# 3.net
KiCad netlist of a schematic drawn in Altium Designer
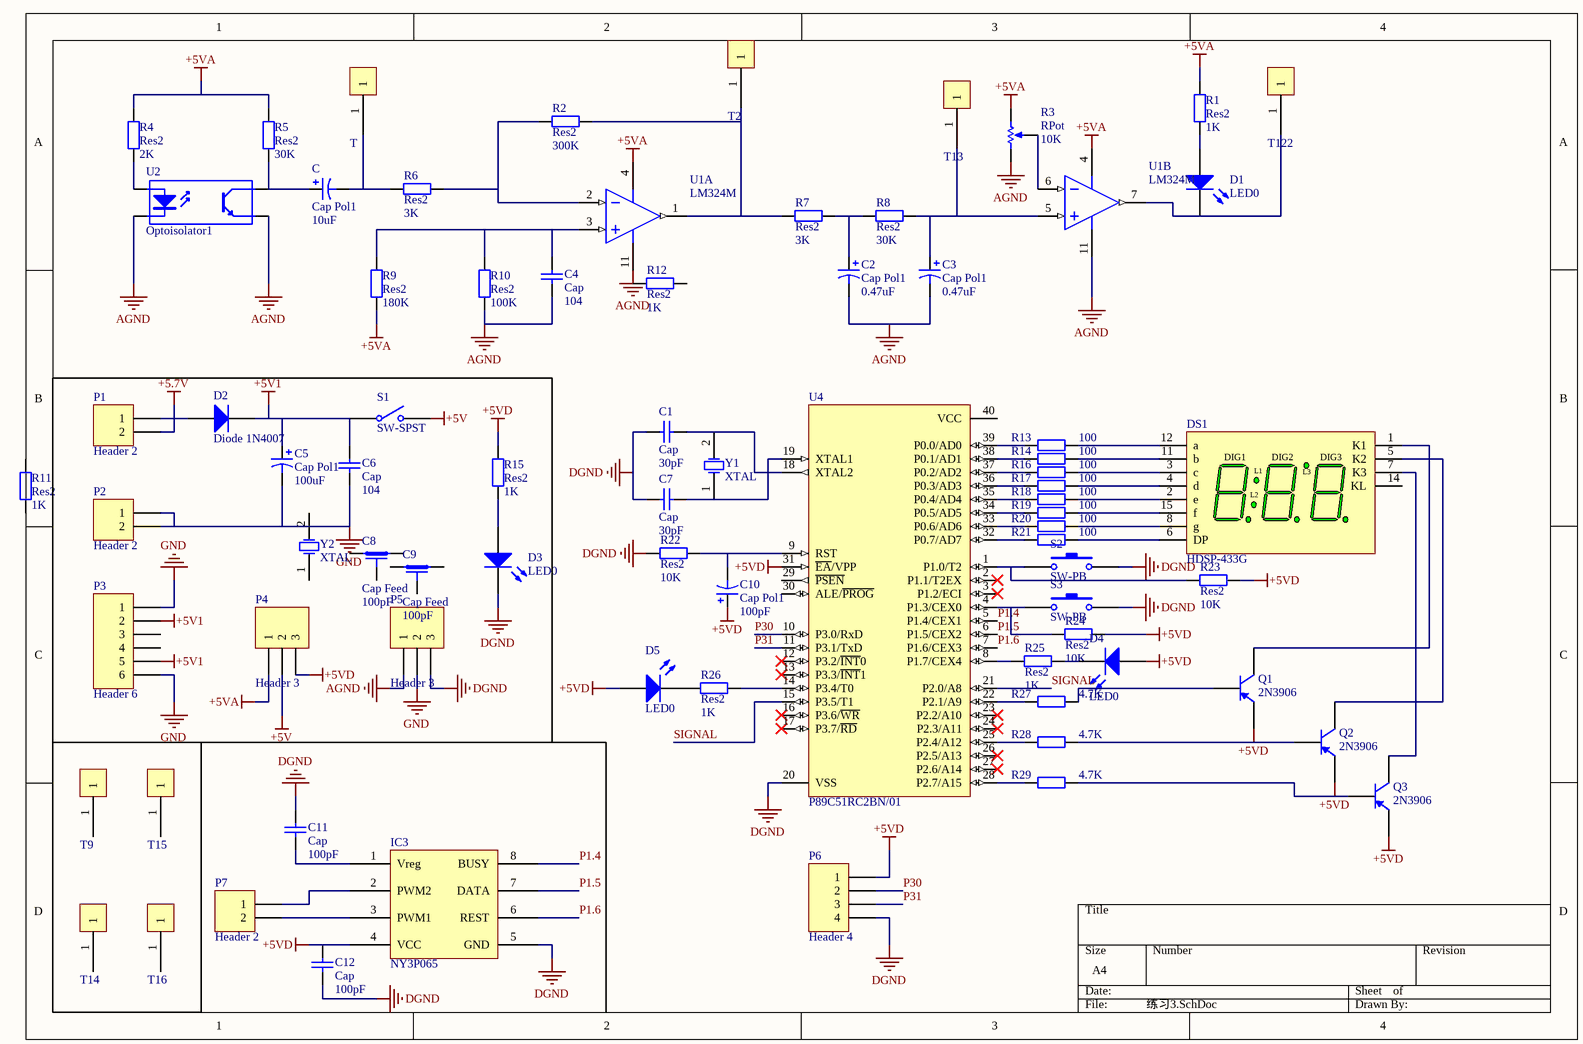
[diagram p0: 练习3.SchDoc]

(export (version "E")
  (design (tool "Eeschema 10.0.6"))
  (components
    (comp (ref "C")
      (value "Cap Pol1")
      (footprint "RB7.6-15")
      (description "Polarized Capacitor (Radial)")
      (fields (field (name "ALTIUM_VALUE") "10uF") (field (name "PUBLISHER") "Altium Limited"))
      (libsource (lib "Miscellaneous Devices") (part "Cap Pol1"))
    )
    (comp (ref "C1")
      (value "Cap")
      (footprint "RAD-0.3")
      (description "Capacitor")
      (fields (field (name "ALTIUM_VALUE") "30pF") (field (name "PUBLISHER") "Altium Limited"))
      (libsource (lib "Miscellaneous Devices") (part "Cap"))
    )
    (comp (ref "C2")
      (value "Cap Pol1")
      (footprint "RB7.6-15")
      (description "Polarized Capacitor (Radial)")
      (fields (field (name "ALTIUM_VALUE") "0.47uF") (field (name "PUBLISHER") "Altium Limited"))
      (libsource (lib "Miscellaneous Devices") (part "Cap Pol1"))
    )
    (comp (ref "C3")
      (value "Cap Pol1")
      (footprint "RB7.6-15")
      (description "Polarized Capacitor (Radial)")
      (fields (field (name "ALTIUM_VALUE") "0.47uF") (field (name "PUBLISHER") "Altium Limited"))
      (libsource (lib "Miscellaneous Devices") (part "Cap Pol1"))
    )
    (comp (ref "C4")
      (value "Cap")
      (footprint "RAD-0.3")
      (description "Capacitor")
      (fields (field (name "ALTIUM_VALUE") "104") (field (name "PUBLISHER") "Altium Limited"))
      (libsource (lib "Miscellaneous Devices") (part "Cap"))
    )
    (comp (ref "C5")
      (value "Cap Pol1")
      (footprint "RB7.6-15")
      (description "Polarized Capacitor (Radial)")
      (fields (field (name "ALTIUM_VALUE") "100uF") (field (name "PUBLISHER") "Altium Limited"))
      (libsource (lib "Miscellaneous Devices") (part "Cap Pol1"))
    )
    (comp (ref "C6")
      (value "Cap")
      (footprint "RAD-0.3")
      (description "Capacitor")
      (fields (field (name "ALTIUM_VALUE") "104") (field (name "PUBLISHER") "Altium Limited"))
      (libsource (lib "Miscellaneous Devices") (part "Cap"))
    )
    (comp (ref "C7")
      (value "Cap")
      (footprint "RAD-0.3")
      (description "Capacitor")
      (fields (field (name "ALTIUM_VALUE") "30pF") (field (name "PUBLISHER") "Altium Limited"))
      (libsource (lib "Miscellaneous Devices") (part "Cap"))
    )
    (comp (ref "C8")
      (value "Cap Feed")
      (footprint "VR4")
      (description "Feed-Through Capacitor")
      (fields (field (name "ALTIUM_VALUE") "100pF") (field (name "PUBLISHER") "Altium Limited"))
      (libsource (lib "Miscellaneous Devices") (part "Cap Feed"))
    )
    (comp (ref "C9")
      (value "Cap Feed")
      (footprint "VR4")
      (description "Feed-Through Capacitor")
      (fields (field (name "ALTIUM_VALUE") "100pF") (field (name "PUBLISHER") "Altium Limited"))
      (libsource (lib "Miscellaneous Devices") (part "Cap Feed"))
    )
    (comp (ref "C10")
      (value "Cap Pol1")
      (footprint "RB7.6-15")
      (description "Polarized Capacitor (Radial)")
      (fields (field (name "ALTIUM_VALUE") "100pF") (field (name "PUBLISHER") "Altium Limited"))
      (libsource (lib "Miscellaneous Devices") (part "Cap Pol1"))
    )
    (comp (ref "C11")
      (value "Cap")
      (footprint "RAD-0.3")
      (description "Capacitor")
      (fields (field (name "ALTIUM_VALUE") "100pF") (field (name "PUBLISHER") "Altium Limited"))
      (libsource (lib "Miscellaneous Devices") (part "Cap"))
    )
    (comp (ref "C12")
      (value "Cap")
      (footprint "RAD-0.3")
      (description "Capacitor")
      (fields (field (name "ALTIUM_VALUE") "100pF") (field (name "PUBLISHER") "Altium Limited"))
      (libsource (lib "Miscellaneous Devices") (part "Cap"))
    )
    (comp (ref "D1")
      (value "LED0")
      (footprint "LED-0")
      (description "Typical INFRARED GaAs LED")
      (fields (field (name "PUBLISHER") "Altium Limited"))
      (libsource (lib "Miscellaneous Devices") (part "LED0"))
    )
    (comp (ref "D2")
      (value "Diode 1N4007")
      (footprint "DO-41")
      (description "1 Amp General Purpose Rectifier")
      (fields (field (name "PUBLISHER") "Altium Limited"))
      (libsource (lib "Miscellaneous Devices") (part "Diode 1N4007"))
    )
    (comp (ref "D3")
      (value "LED0")
      (footprint "LED-0")
      (description "Typical INFRARED GaAs LED")
      (fields (field (name "PUBLISHER") "Altium Limited"))
      (libsource (lib "Miscellaneous Devices") (part "LED0"))
    )
    (comp (ref "D4")
      (value "LED0")
      (footprint "LED-0")
      (description "Typical INFRARED GaAs LED")
      (fields (field (name "PUBLISHER") "Altium Limited"))
      (libsource (lib "Miscellaneous Devices") (part "LED0"))
    )
    (comp (ref "D5")
      (value "LED0")
      (footprint "LED-0")
      (description "Typical INFRARED GaAs LED")
      (fields (field (name "PUBLISHER") "Altium Limited"))
      (libsource (lib "Miscellaneous Devices") (part "LED0"))
    )
    (comp (ref "DS1")
      (value "HDSP-433G")
      (footprint "HDSP-4")
      (description "10 mm Gray Surface 7-Segment Display: 3-Digit with 2-Colons, CC, Slim Font, Untinted-Diffused")
      (fields (field (name "PUBLISHER") "Altium Limited"))
      (libsource (lib "Agilent LED Display 7-Segment, 3-Digit") (part "HDSP-433G"))
    )
    (comp (ref "IC3") (value "NY3P065") (footprint "SO8MY") (libsource (lib "EPL Scblib") (part "SOUND")))
    (comp (ref "P1")
      (value "Header 2")
      (footprint "HDR1X2")
      (description "Header, 2-Pin")
      (fields (field (name "PUBLISHER") "Altium Limited"))
      (libsource (lib "Miscellaneous Connectors") (part "Header 2"))
    )
    (comp (ref "P2")
      (value "Header 2")
      (footprint "HDR1X2")
      (description "Header, 2-Pin")
      (fields (field (name "PUBLISHER") "Altium Limited"))
      (libsource (lib "Miscellaneous Connectors") (part "Header 2"))
    )
    (comp (ref "P3")
      (value "Header 6")
      (footprint "HDR1X6")
      (description "Header, 6-Pin")
      (fields (field (name "PUBLISHER") "Altium Limited"))
      (libsource (lib "Miscellaneous Connectors") (part "Header 6"))
    )
    (comp (ref "P4")
      (value "Header 3")
      (footprint "HDR1X3")
      (description "Header, 3-Pin")
      (fields (field (name "PUBLISHER") "Altium Limited"))
      (libsource (lib "Miscellaneous Connectors") (part "Header 3"))
    )
    (comp (ref "P5")
      (value "Header 3")
      (footprint "HDR1X3")
      (description "Header, 3-Pin")
      (fields (field (name "PUBLISHER") "Altium Limited"))
      (libsource (lib "Miscellaneous Connectors") (part "Header 3"))
    )
    (comp (ref "P6")
      (value "Header 4")
      (footprint "HDR1X4")
      (description "Header, 4-Pin")
      (fields (field (name "PUBLISHER") "Altium Limited"))
      (libsource (lib "Miscellaneous Connectors") (part "Header 4"))
    )
    (comp (ref "P7")
      (value "Header 2")
      (footprint "HDR1X2")
      (description "Header, 2-Pin")
      (fields (field (name "PUBLISHER") "Altium Limited"))
      (libsource (lib "Miscellaneous Connectors") (part "Header 2"))
    )
    (comp (ref "Q1")
      (value "2N3906")
      (footprint "TO-92A")
      (description "PNP General Purpose Amplifier")
      (fields (field (name "PUBLISHER") "Altium Limited"))
      (libsource (lib "Miscellaneous Devices") (part "2N3906"))
    )
    (comp (ref "Q2")
      (value "2N3906")
      (footprint "TO-92A")
      (description "PNP General Purpose Amplifier")
      (fields (field (name "PUBLISHER") "Altium Limited"))
      (libsource (lib "Miscellaneous Devices") (part "2N3906"))
    )
    (comp (ref "Q3")
      (value "2N3906")
      (footprint "TO-92A")
      (description "PNP General Purpose Amplifier")
      (fields (field (name "PUBLISHER") "Altium Limited"))
      (libsource (lib "Miscellaneous Devices") (part "2N3906"))
    )
    (comp (ref "R1")
      (value "Res2")
      (footprint "AXIAL-0.4")
      (description "Resistor")
      (fields (field (name "ALTIUM_VALUE") "1K") (field (name "PUBLISHER") "Altium Limited"))
      (libsource (lib "") (part "Res2_2"))
    )
    (comp (ref "R2")
      (value "Res2")
      (footprint "AXIAL-0.4")
      (description "Resistor")
      (fields (field (name "ALTIUM_VALUE") "300K") (field (name "PUBLISHER") "Altium Limited"))
      (libsource (lib "Miscellaneous Devices") (part "Res2"))
    )
    (comp (ref "R3")
      (value "RPot")
      (footprint "VR5")
      (description "Potentiometer")
      (fields (field (name "ALTIUM_VALUE") "10K") (field (name "PUBLISHER") "Altium Limited"))
      (libsource (lib "Miscellaneous Devices") (part "RPot"))
    )
    (comp (ref "R4")
      (value "Res2")
      (footprint "AXIAL-0.4")
      (description "Resistor")
      (fields (field (name "ALTIUM_VALUE") "2K") (field (name "PUBLISHER") "Altium Limited"))
      (libsource (lib "") (part "Res2_2"))
    )
    (comp (ref "R5")
      (value "Res2")
      (footprint "AXIAL-0.4")
      (description "Resistor")
      (fields (field (name "ALTIUM_VALUE") "30K") (field (name "PUBLISHER") "Altium Limited"))
      (libsource (lib "") (part "Res2_2"))
    )
    (comp (ref "R6")
      (value "Res2")
      (footprint "AXIAL-0.4")
      (description "Resistor")
      (fields (field (name "ALTIUM_VALUE") "3K") (field (name "PUBLISHER") "Altium Limited"))
      (libsource (lib "Miscellaneous Devices") (part "Res2"))
    )
    (comp (ref "R7")
      (value "Res2")
      (footprint "AXIAL-0.4")
      (description "Resistor")
      (fields (field (name "ALTIUM_VALUE") "3K") (field (name "PUBLISHER") "Altium Limited"))
      (libsource (lib "Miscellaneous Devices") (part "Res2"))
    )
    (comp (ref "R8")
      (value "Res2")
      (footprint "AXIAL-0.4")
      (description "Resistor")
      (fields (field (name "ALTIUM_VALUE") "30K") (field (name "PUBLISHER") "Altium Limited"))
      (libsource (lib "Miscellaneous Devices") (part "Res2"))
    )
    (comp (ref "R9")
      (value "Res2")
      (footprint "AXIAL-0.4")
      (description "Resistor")
      (fields (field (name "ALTIUM_VALUE") "180K") (field (name "PUBLISHER") "Altium Limited"))
      (libsource (lib "") (part "Res2_1"))
    )
    (comp (ref "R10")
      (value "Res2")
      (footprint "AXIAL-0.4")
      (description "Resistor")
      (fields (field (name "ALTIUM_VALUE") "100K") (field (name "PUBLISHER") "Altium Limited"))
      (libsource (lib "") (part "Res2_1"))
    )
    (comp (ref "R11")
      (value "Res2")
      (footprint "AXIAL-0.4")
      (description "Resistor")
      (fields (field (name "ALTIUM_VALUE") "1K") (field (name "PUBLISHER") "Altium Limited"))
      (libsource (lib "") (part "Res2_1"))
    )
    (comp (ref "R12")
      (value "Res2")
      (footprint "AXIAL-0.4")
      (description "Resistor")
      (fields (field (name "ALTIUM_VALUE") "1K") (field (name "PUBLISHER") "Altium Limited"))
      (libsource (lib "Miscellaneous Devices") (part "Res2"))
    )
    (comp (ref "R13")
      (value "100")
      (footprint "AXIAL-0.4")
      (description "Resistor")
      (fields (field (name "PUBLISHER") "Altium Limited"))
      (libsource (lib "Miscellaneous Devices") (part "Res2"))
    )
    (comp (ref "R14")
      (value "100")
      (footprint "AXIAL-0.4")
      (description "Resistor")
      (fields (field (name "PUBLISHER") "Altium Limited"))
      (libsource (lib "Miscellaneous Devices") (part "Res2"))
    )
    (comp (ref "R15")
      (value "Res2")
      (footprint "AXIAL-0.4")
      (description "Resistor")
      (fields (field (name "ALTIUM_VALUE") "1K") (field (name "PUBLISHER") "Altium Limited"))
      (libsource (lib "") (part "Res2_1"))
    )
    (comp (ref "R16")
      (value "100")
      (footprint "AXIAL-0.4")
      (description "Resistor")
      (fields (field (name "PUBLISHER") "Altium Limited"))
      (libsource (lib "Miscellaneous Devices") (part "Res2"))
    )
    (comp (ref "R17")
      (value "100")
      (footprint "AXIAL-0.4")
      (description "Resistor")
      (fields (field (name "PUBLISHER") "Altium Limited"))
      (libsource (lib "Miscellaneous Devices") (part "Res2"))
    )
    (comp (ref "R18")
      (value "100")
      (footprint "AXIAL-0.4")
      (description "Resistor")
      (fields (field (name "PUBLISHER") "Altium Limited"))
      (libsource (lib "Miscellaneous Devices") (part "Res2"))
    )
    (comp (ref "R19")
      (value "100")
      (footprint "AXIAL-0.4")
      (description "Resistor")
      (fields (field (name "PUBLISHER") "Altium Limited"))
      (libsource (lib "Miscellaneous Devices") (part "Res2"))
    )
    (comp (ref "R20")
      (value "100")
      (footprint "AXIAL-0.4")
      (description "Resistor")
      (fields (field (name "PUBLISHER") "Altium Limited"))
      (libsource (lib "Miscellaneous Devices") (part "Res2"))
    )
    (comp (ref "R21")
      (value "100")
      (footprint "AXIAL-0.4")
      (description "Resistor")
      (fields (field (name "PUBLISHER") "Altium Limited"))
      (libsource (lib "Miscellaneous Devices") (part "Res2"))
    )
    (comp (ref "R22")
      (value "Res2")
      (footprint "AXIAL-0.4")
      (description "Resistor")
      (fields (field (name "ALTIUM_VALUE") "10K") (field (name "PUBLISHER") "Altium Limited"))
      (libsource (lib "Miscellaneous Devices") (part "Res2"))
    )
    (comp (ref "R23")
      (value "Res2")
      (footprint "AXIAL-0.4")
      (description "Resistor")
      (fields (field (name "ALTIUM_VALUE") "10K") (field (name "PUBLISHER") "Altium Limited"))
      (libsource (lib "Miscellaneous Devices") (part "Res2"))
    )
    (comp (ref "R24")
      (value "Res2")
      (footprint "AXIAL-0.4")
      (description "Resistor")
      (fields (field (name "ALTIUM_VALUE") "10K") (field (name "PUBLISHER") "Altium Limited"))
      (libsource (lib "Miscellaneous Devices") (part "Res2"))
    )
    (comp (ref "R25")
      (value "Res2")
      (footprint "AXIAL-0.4")
      (description "Resistor")
      (fields (field (name "ALTIUM_VALUE") "1K") (field (name "PUBLISHER") "Altium Limited"))
      (libsource (lib "Miscellaneous Devices") (part "Res2"))
    )
    (comp (ref "R26")
      (value "Res2")
      (footprint "AXIAL-0.4")
      (description "Resistor")
      (fields (field (name "ALTIUM_VALUE") "1K") (field (name "PUBLISHER") "Altium Limited"))
      (libsource (lib "Miscellaneous Devices") (part "Res2"))
    )
    (comp (ref "R27")
      (value "4.7K")
      (footprint "AXIAL-0.4")
      (description "Resistor")
      (fields (field (name "PUBLISHER") "Altium Limited"))
      (libsource (lib "Miscellaneous Devices") (part "Res2"))
    )
    (comp (ref "R28")
      (value "4.7K")
      (footprint "AXIAL-0.4")
      (description "Resistor")
      (fields (field (name "PUBLISHER") "Altium Limited"))
      (libsource (lib "Miscellaneous Devices") (part "Res2"))
    )
    (comp (ref "R29")
      (value "4.7K")
      (footprint "AXIAL-0.4")
      (description "Resistor")
      (fields (field (name "PUBLISHER") "Altium Limited"))
      (libsource (lib "Miscellaneous Devices") (part "Res2"))
    )
    (comp (ref "S1")
      (value "SW-SPST")
      (footprint "SPST-2")
      (description "Single-Pole, Single-Throw Switch")
      (fields (field (name "PUBLISHER") "Altium Limited"))
      (libsource (lib "Miscellaneous Devices") (part "SW-SPST"))
    )
    (comp (ref "S2")
      (value "SW-PB")
      (footprint "SPST-2")
      (description "Switch")
      (fields (field (name "PUBLISHER") "Altium Limited"))
      (libsource (lib "Miscellaneous Devices") (part "SW-PB"))
    )
    (comp (ref "S3")
      (value "SW-PB")
      (footprint "SPST-2")
      (description "Switch")
      (fields (field (name "PUBLISHER") "Altium Limited"))
      (libsource (lib "Miscellaneous Devices") (part "SW-PB"))
    )
    (comp (ref "T") (value "TEST") (footprint "SIP1") (libsource (lib "EPL Scblib") (part "TEST")))
    (comp (ref "T2") (value "TEST") (footprint "SIP1") (libsource (lib "EPL Scblib") (part "TEST")))
    (comp (ref "T9") (value "TEST") (footprint "SIP1") (libsource (lib "EPL Scblib") (part "TEST")))
    (comp (ref "T13") (value "TEST") (footprint "SIP1") (libsource (lib "EPL Scblib") (part "TEST")))
    (comp (ref "T14") (value "TEST") (footprint "SIP1") (libsource (lib "EPL Scblib") (part "TEST")))
    (comp (ref "T15") (value "TEST") (footprint "SIP1") (libsource (lib "EPL Scblib") (part "TEST")))
    (comp (ref "T16") (value "TEST") (footprint "SIP1") (libsource (lib "EPL Scblib") (part "TEST")))
    (comp (ref "T122") (value "TEST") (footprint "SIP1") (libsource (lib "EPL Scblib") (part "TEST")))
    (comp (ref "U1")
      (value "LM324M")
      (footprint "M14A_N")
      (description "Low Power Quad Operational Amplifier")
      (fields
        (field (name "MANUFACTURER") "National Semiconductor")
        (field (name "DIGIKEYPARTNUMBER") "LM324MXCT-ND")
        (field (name "PUBLISHER") "Altium Limited")
      )
      (libsource (lib "NSC Amplifier") (part "LM324M"))
    )
    (comp (ref "U2")
      (value "Optoisolator1")
      (footprint "DIP-4")
      (description "4-Pin Phototransistor Optocoupler")
      (fields (field (name "PUBLISHER") "Altium Limited"))
      (libsource (lib "Miscellaneous Devices") (part "Optoisolator1"))
    )
    (comp (ref "U4")
      (value "P89C51RC2BN/01")
      (footprint "SOT129-1")
      (description "80C51 8-Bit Flash Microcontroller Family, 32 kB ISP/IAP Flash with 512 B RAM.")
      (fields (field (name "PUBLISHER") "Altium Limited"))
      (libsource (lib "Philips Microcontroller 8-Bit") (part "P89C51RC2BN/01"))
    )
    (comp (ref "Y1")
      (value "XTAL")
      (footprint "R38")
      (description "Crystal Oscillator")
      (fields (field (name "PUBLISHER") "Altium Limited"))
      (libsource (lib "Miscellaneous Devices") (part "XTAL"))
    )
    (comp (ref "Y2")
      (value "XTAL")
      (footprint "R38")
      (description "Crystal Oscillator")
      (fields (field (name "PUBLISHER") "Altium Limited"))
      (libsource (lib "Miscellaneous Devices") (part "XTAL"))
    )
  )
  (nets
    (net (code "1") (name "+5.7V") (class "Default")
      (node (ref "D2") (pin "1") (pinfunction "A_1") (pintype "passive"))
      (node (ref "P1") (pin "1") (pinfunction "1_1") (pintype "passive"))
      (node (ref "P1") (pin "2") (pinfunction "2_2") (pintype "passive"))
    )
    (net (code "2") (name "+5V") (class "Default")
      (node (ref "P4") (pin "2") (pinfunction "2_2") (pintype "passive"))
      (node (ref "S1") (pin "2") (pinfunction "NO_2") (pintype "passive"))
    )
    (net (code "3") (name "+5V1") (class "Default")
      (node (ref "C5") (pin "1") (pinfunction "1_1") (pintype "passive"))
      (node (ref "C6") (pin "1") (pinfunction "1_1") (pintype "passive"))
      (node (ref "D2") (pin "2") (pinfunction "K_2") (pintype "passive"))
      (node (ref "P3") (pin "2") (pinfunction "2_2") (pintype "passive"))
      (node (ref "P3") (pin "5") (pinfunction "5_5") (pintype "passive"))
      (node (ref "S1") (pin "1") (pinfunction "COMMON_1") (pintype "passive"))
    )
    (net (code "4") (name "+5VA") (class "Default")
      (node (ref "P4") (pin "1") (pinfunction "1_1") (pintype "passive"))
      (node (ref "R1") (pin "2") (pinfunction "2_2") (pintype "passive"))
      (node (ref "R3") (pin "2") (pinfunction "BOT_2") (pintype "passive"))
      (node (ref "R4") (pin "2") (pinfunction "2_2") (pintype "passive"))
      (node (ref "R5") (pin "2") (pinfunction "2_2") (pintype "passive"))
      (node (ref "R9") (pin "2") (pinfunction "2_2") (pintype "passive"))
      (node (ref "U1") (pin "4") (pinfunction "V+_4") (pintype "power_in"))
    )
    (net (code "5") (name "+5VD") (class "Default")
      (node (ref "C10") (pin "1") (pinfunction "1_1") (pintype "passive"))
      (node (ref "C12") (pin "2") (pinfunction "2_2") (pintype "passive"))
      (node (ref "D4") (pin "1") (pinfunction "A_1") (pintype "passive"))
      (node (ref "D5") (pin "1") (pinfunction "A_1") (pintype "passive"))
      (node (ref "IC3") (pin "4") (pinfunction "VCC_4") (pintype "passive"))
      (node (ref "P4") (pin "3") (pinfunction "3_3") (pintype "passive"))
      (node (ref "P6") (pin "1") (pinfunction "1_1") (pintype "passive"))
      (node (ref "Q1") (pin "1") (pinfunction "E_1") (pintype "passive"))
      (node (ref "Q2") (pin "1") (pinfunction "E_1") (pintype "passive"))
      (node (ref "Q3") (pin "1") (pinfunction "E_1") (pintype "passive"))
      (node (ref "R15") (pin "1") (pinfunction "1_1") (pintype "passive"))
      (node (ref "R23") (pin "2") (pinfunction "2_2") (pintype "passive"))
      (node (ref "R24") (pin "2") (pinfunction "2_2") (pintype "passive"))
      (node (ref "U4") (pin "31") (pinfunction "~{EA}/VPP_31") (pintype "input"))
    )
    (net (code "6") (name "/P1.4") (class "Default")
      (node (ref "IC3") (pin "8") (pinfunction "BUSY_8") (pintype "passive"))
      (node (ref "U4") (pin "5") (pinfunction "P1.4/CEX1_5") (pintype "bidirectional"))
    )
    (net (code "7") (name "/P1.5") (class "Default")
      (node (ref "IC3") (pin "7") (pinfunction "DATA_7") (pintype "passive"))
      (node (ref "U4") (pin "6") (pinfunction "P1.5/CEX2_6") (pintype "bidirectional"))
    )
    (net (code "8") (name "/P1.6") (class "Default")
      (node (ref "IC3") (pin "6") (pinfunction "REST_6") (pintype "passive"))
      (node (ref "U4") (pin "7") (pinfunction "P1.6/CEX3_7") (pintype "bidirectional"))
    )
    (net (code "9") (name "/P30") (class "Default")
      (node (ref "P6") (pin "2") (pinfunction "2_2") (pintype "passive"))
      (node (ref "U4") (pin "10") (pinfunction "P3.0/RxD_10") (pintype "bidirectional"))
    )
    (net (code "10") (name "/P31") (class "Default")
      (node (ref "P6") (pin "3") (pinfunction "3_3") (pintype "passive"))
      (node (ref "U4") (pin "11") (pinfunction "P3.1/TxD_11") (pintype "bidirectional"))
    )
    (net (code "11") (name "/SIGNAL") (class "Default")
      (node (ref "U4") (pin "15") (pinfunction "P3.5/T1_15") (pintype "bidirectional"))
      (node (ref "U4") (pin "21") (pinfunction "P2.0/A8_21") (pintype "bidirectional"))
    )
    (net (code "12") (name "AGND") (class "Default")
      (node (ref "C2") (pin "2") (pinfunction "2_2") (pintype "passive"))
      (node (ref "C3") (pin "2") (pinfunction "2_2") (pintype "passive"))
      (node (ref "C4") (pin "1") (pinfunction "1_1") (pintype "passive"))
      (node (ref "P5") (pin "1") (pinfunction "1_1") (pintype "passive"))
      (node (ref "R10") (pin "2") (pinfunction "2_2") (pintype "passive"))
      (node (ref "R3") (pin "1") (pinfunction "TOP_1") (pintype "passive"))
      (node (ref "U1") (pin "11") (pinfunction "GND_11") (pintype "power_in"))
      (node (ref "U2") (pin "2") (pinfunction "K_2") (pintype "passive"))
      (node (ref "U2") (pin "3") (pinfunction "E_3") (pintype "passive"))
    )
    (net (code "13") (name "DGND") (class "Default")
      (node (ref "C1") (pin "1") (pinfunction "1_1") (pintype "passive"))
      (node (ref "C11") (pin "2") (pinfunction "2_2") (pintype "passive"))
      (node (ref "C12") (pin "1") (pinfunction "1_1") (pintype "passive"))
      (node (ref "C7") (pin "2") (pinfunction "2_2") (pintype "passive"))
      (node (ref "D3") (pin "2") (pinfunction "K_2") (pintype "passive"))
      (node (ref "IC3") (pin "5") (pinfunction "GND_5") (pintype "passive"))
      (node (ref "P5") (pin "3") (pinfunction "3_3") (pintype "passive"))
      (node (ref "P6") (pin "4") (pinfunction "4_4") (pintype "passive"))
      (node (ref "R22") (pin "1") (pinfunction "1_1") (pintype "passive"))
      (node (ref "S2") (pin "2") (pinfunction "2_2") (pintype "passive"))
      (node (ref "S3") (pin "2") (pinfunction "2_2") (pintype "passive"))
      (node (ref "U4") (pin "20") (pinfunction "VSS_20") (pintype "power_in"))
    )
    (net (code "14") (name "GND") (class "Default")
      (node (ref "C5") (pin "2") (pinfunction "2_2") (pintype "passive"))
      (node (ref "C6") (pin "2") (pinfunction "2_2") (pintype "passive"))
      (node (ref "P2") (pin "1") (pinfunction "1_1") (pintype "passive"))
      (node (ref "P2") (pin "2") (pinfunction "2_2") (pintype "passive"))
      (node (ref "P3") (pin "1") (pinfunction "1_1") (pintype "passive"))
      (node (ref "P3") (pin "6") (pinfunction "6_6") (pintype "passive"))
      (node (ref "P5") (pin "2") (pinfunction "2_2") (pintype "passive"))
    )
    (net (code "15") (name "Net-(C-Pad2)") (class "Default")
      (node (ref "C") (pin "2") (pinfunction "2_2") (pintype "passive"))
      (node (ref "R6") (pin "1") (pinfunction "1_1") (pintype "passive"))
      (node (ref "T") (pin "1") (pinfunction "1_1") (pintype "passive"))
    )
    (net (code "16") (name "Net-(C2-Pad1)") (class "Default")
      (node (ref "C2") (pin "1") (pinfunction "1_1") (pintype "passive"))
      (node (ref "R7") (pin "2") (pinfunction "2_2") (pintype "passive"))
      (node (ref "R8") (pin "1") (pinfunction "1_1") (pintype "passive"))
    )
    (net (code "17") (name "Net-(D1-A)") (class "Default")
      (node (ref "D1") (pin "1") (pinfunction "A_1") (pintype "passive"))
      (node (ref "R1") (pin "1") (pinfunction "1_1") (pintype "passive"))
    )
    (net (code "18") (name "Net-(D1-K)") (class "Default")
      (node (ref "D1") (pin "2") (pinfunction "K_2") (pintype "passive"))
      (node (ref "T122") (pin "1") (pinfunction "1_1") (pintype "passive"))
      (node (ref "U1") (pin "7") (pinfunction "OUT2_7") (pintype "output"))
    )
    (net (code "19") (name "Net-(D3-A)") (class "Default")
      (node (ref "D3") (pin "1") (pinfunction "A_1") (pintype "passive"))
      (node (ref "R15") (pin "2") (pinfunction "2_2") (pintype "passive"))
    )
    (net (code "20") (name "Net-(D4-K)") (class "Default")
      (node (ref "D4") (pin "2") (pinfunction "K_2") (pintype "passive"))
      (node (ref "R25") (pin "2") (pinfunction "2_2") (pintype "passive"))
    )
    (net (code "21") (name "Net-(D5-K)") (class "Default")
      (node (ref "D5") (pin "2") (pinfunction "K_2") (pintype "passive"))
      (node (ref "R26") (pin "1") (pinfunction "1_1") (pintype "passive"))
    )
    (net (code "22") (name "Net-(DS1-DP)") (class "Default")
      (node (ref "DS1") (pin "6") (pinfunction "DP_6") (pintype "passive"))
      (node (ref "R21") (pin "2") (pinfunction "2_2") (pintype "passive"))
    )
    (net (code "23") (name "Net-(DS1-K1)") (class "Default")
      (node (ref "DS1") (pin "1") (pinfunction "K1_1") (pintype "passive"))
      (node (ref "Q1") (pin "3") (pinfunction "C_3") (pintype "passive"))
    )
    (net (code "24") (name "Net-(DS1-K2)") (class "Default")
      (node (ref "DS1") (pin "5") (pinfunction "K2_5") (pintype "passive"))
      (node (ref "Q2") (pin "3") (pinfunction "C_3") (pintype "passive"))
    )
    (net (code "25") (name "Net-(DS1-K3)") (class "Default")
      (node (ref "DS1") (pin "7") (pinfunction "K3_7") (pintype "passive"))
      (node (ref "Q3") (pin "3") (pinfunction "C_3") (pintype "passive"))
    )
    (net (code "26") (name "Net-(DS1-a)") (class "Default")
      (node (ref "DS1") (pin "12") (pinfunction "a_12") (pintype "passive"))
      (node (ref "R13") (pin "2") (pinfunction "2_2") (pintype "passive"))
    )
    (net (code "27") (name "Net-(DS1-b)") (class "Default")
      (node (ref "DS1") (pin "11") (pinfunction "b_11") (pintype "passive"))
      (node (ref "R14") (pin "2") (pinfunction "2_2") (pintype "passive"))
    )
    (net (code "28") (name "Net-(DS1-c)") (class "Default")
      (node (ref "DS1") (pin "3") (pinfunction "c_3") (pintype "passive"))
      (node (ref "R16") (pin "2") (pinfunction "2_2") (pintype "passive"))
    )
    (net (code "29") (name "Net-(DS1-d)") (class "Default")
      (node (ref "DS1") (pin "4") (pinfunction "d_4") (pintype "passive"))
      (node (ref "R17") (pin "2") (pinfunction "2_2") (pintype "passive"))
    )
    (net (code "30") (name "Net-(DS1-e)") (class "Default")
      (node (ref "DS1") (pin "2") (pinfunction "e_2") (pintype "passive"))
      (node (ref "R18") (pin "2") (pinfunction "2_2") (pintype "passive"))
    )
    (net (code "31") (name "Net-(DS1-f)") (class "Default")
      (node (ref "DS1") (pin "15") (pinfunction "f_15") (pintype "passive"))
      (node (ref "R19") (pin "2") (pinfunction "2_2") (pintype "passive"))
    )
    (net (code "32") (name "Net-(DS1-g)") (class "Default")
      (node (ref "DS1") (pin "8") (pinfunction "g_8") (pintype "passive"))
      (node (ref "R20") (pin "2") (pinfunction "2_2") (pintype "passive"))
    )
    (net (code "33") (name "Net-(IC3-PWM1)") (class "Default")
      (node (ref "IC3") (pin "3") (pinfunction "PWM1_3") (pintype "passive"))
      (node (ref "P7") (pin "2") (pinfunction "2_2") (pintype "passive"))
    )
    (net (code "34") (name "Net-(IC3-PWM2)") (class "Default")
      (node (ref "IC3") (pin "2") (pinfunction "PWM2_2") (pintype "passive"))
      (node (ref "P7") (pin "1") (pinfunction "1_1") (pintype "passive"))
    )
    (net (code "35") (name "Net-(IC3-Vreg)") (class "Default")
      (node (ref "C11") (pin "1") (pinfunction "1_1") (pintype "passive"))
      (node (ref "IC3") (pin "1") (pinfunction "Vreg_1") (pintype "passive"))
    )
    (net (code "36") (name "Net-(Q1-B)") (class "Default")
      (node (ref "Q1") (pin "2") (pinfunction "B_2") (pintype "passive"))
      (node (ref "R27") (pin "2") (pinfunction "2_2") (pintype "passive"))
    )
    (net (code "37") (name "Net-(Q2-B)") (class "Default")
      (node (ref "Q2") (pin "2") (pinfunction "B_2") (pintype "passive"))
      (node (ref "R28") (pin "2") (pinfunction "2_2") (pintype "passive"))
    )
    (net (code "38") (name "Net-(Q3-B)") (class "Default")
      (node (ref "Q3") (pin "2") (pinfunction "B_2") (pintype "passive"))
      (node (ref "R29") (pin "2") (pinfunction "2_2") (pintype "passive"))
    )
    (net (code "39") (name "Net-(R3-TAP)") (class "Default")
      (node (ref "R3") (pin "3") (pinfunction "TAP_3") (pintype "passive"))
      (node (ref "U1") (pin "6") (pinfunction "IN2-_6") (pintype "input"))
    )
    (net (code "40") (name "Net-(U1A-IN1+)") (class "Default")
      (node (ref "C4") (pin "2") (pinfunction "2_2") (pintype "passive"))
      (node (ref "R10") (pin "1") (pinfunction "1_1") (pintype "passive"))
      (node (ref "R9") (pin "1") (pinfunction "1_1") (pintype "passive"))
      (node (ref "U1") (pin "3") (pinfunction "IN1+_3") (pintype "input"))
    )
    (net (code "41") (name "Net-(U1A-IN1-)") (class "Default")
      (node (ref "R2") (pin "1") (pinfunction "1_1") (pintype "passive"))
      (node (ref "R6") (pin "2") (pinfunction "2_2") (pintype "passive"))
      (node (ref "U1") (pin "2") (pinfunction "IN1-_2") (pintype "input"))
    )
    (net (code "42") (name "Net-(U1A-OUT1)") (class "Default")
      (node (ref "R2") (pin "2") (pinfunction "2_2") (pintype "passive"))
      (node (ref "R7") (pin "1") (pinfunction "1_1") (pintype "passive"))
      (node (ref "T2") (pin "1") (pinfunction "1_1") (pintype "passive"))
      (node (ref "U1") (pin "1") (pinfunction "OUT1_1") (pintype "output"))
    )
    (net (code "43") (name "Net-(U1B-IN2+)") (class "Default")
      (node (ref "C3") (pin "1") (pinfunction "1_1") (pintype "passive"))
      (node (ref "R8") (pin "2") (pinfunction "2_2") (pintype "passive"))
      (node (ref "T13") (pin "1") (pinfunction "1_1") (pintype "passive"))
      (node (ref "U1") (pin "5") (pinfunction "IN2+_5") (pintype "input"))
    )
    (net (code "44") (name "Net-(U2-A)") (class "Default")
      (node (ref "R4") (pin "1") (pinfunction "1_1") (pintype "passive"))
      (node (ref "U2") (pin "1") (pinfunction "A_1") (pintype "passive"))
    )
    (net (code "45") (name "Net-(U2-C)") (class "Default")
      (node (ref "C") (pin "1") (pinfunction "1_1") (pintype "passive"))
      (node (ref "R5") (pin "1") (pinfunction "1_1") (pintype "passive"))
      (node (ref "U2") (pin "4") (pinfunction "C_4") (pintype "passive"))
    )
    (net (code "46") (name "Net-(U4-P0.0{slash}AD0)") (class "Default")
      (node (ref "R13") (pin "1") (pinfunction "1_1") (pintype "passive"))
      (node (ref "U4") (pin "39") (pinfunction "P0.0/AD0_39") (pintype "bidirectional"))
    )
    (net (code "47") (name "Net-(U4-P0.1{slash}AD1)") (class "Default")
      (node (ref "R14") (pin "1") (pinfunction "1_1") (pintype "passive"))
      (node (ref "U4") (pin "38") (pinfunction "P0.1/AD1_38") (pintype "bidirectional"))
    )
    (net (code "48") (name "Net-(U4-P0.2{slash}AD2)") (class "Default")
      (node (ref "R16") (pin "1") (pinfunction "1_1") (pintype "passive"))
      (node (ref "U4") (pin "37") (pinfunction "P0.2/AD2_37") (pintype "bidirectional"))
    )
    (net (code "49") (name "Net-(U4-P0.3{slash}AD3)") (class "Default")
      (node (ref "R17") (pin "1") (pinfunction "1_1") (pintype "passive"))
      (node (ref "U4") (pin "36") (pinfunction "P0.3/AD3_36") (pintype "bidirectional"))
    )
    (net (code "50") (name "Net-(U4-P0.4{slash}AD4)") (class "Default")
      (node (ref "R18") (pin "1") (pinfunction "1_1") (pintype "passive"))
      (node (ref "U4") (pin "35") (pinfunction "P0.4/AD4_35") (pintype "bidirectional"))
    )
    (net (code "51") (name "Net-(U4-P0.5{slash}AD5)") (class "Default")
      (node (ref "R19") (pin "1") (pinfunction "1_1") (pintype "passive"))
      (node (ref "U4") (pin "34") (pinfunction "P0.5/AD5_34") (pintype "bidirectional"))
    )
    (net (code "52") (name "Net-(U4-P0.6{slash}AD6)") (class "Default")
      (node (ref "R20") (pin "1") (pinfunction "1_1") (pintype "passive"))
      (node (ref "U4") (pin "33") (pinfunction "P0.6/AD6_33") (pintype "bidirectional"))
    )
    (net (code "53") (name "Net-(U4-P0.7{slash}AD7)") (class "Default")
      (node (ref "R21") (pin "1") (pinfunction "1_1") (pintype "passive"))
      (node (ref "U4") (pin "32") (pinfunction "P0.7/AD7_32") (pintype "bidirectional"))
    )
    (net (code "54") (name "Net-(U4-P1.0{slash}T2)") (class "Default")
      (node (ref "R23") (pin "1") (pinfunction "1_1") (pintype "passive"))
      (node (ref "S2") (pin "1") (pinfunction "1_1") (pintype "passive"))
      (node (ref "U4") (pin "1") (pinfunction "P1.0/T2_1") (pintype "bidirectional"))
    )
    (net (code "55") (name "Net-(U4-P1.3{slash}CEX0)") (class "Default")
      (node (ref "R24") (pin "1") (pinfunction "1_1") (pintype "passive"))
      (node (ref "S3") (pin "1") (pinfunction "1_1") (pintype "passive"))
      (node (ref "U4") (pin "4") (pinfunction "P1.3/CEX0_4") (pintype "bidirectional"))
    )
    (net (code "56") (name "Net-(U4-P1.7{slash}CEX4)") (class "Default")
      (node (ref "R25") (pin "1") (pinfunction "1_1") (pintype "passive"))
      (node (ref "U4") (pin "8") (pinfunction "P1.7/CEX4_8") (pintype "bidirectional"))
    )
    (net (code "57") (name "Net-(U4-P2.1{slash}A9)") (class "Default")
      (node (ref "R27") (pin "1") (pinfunction "1_1") (pintype "passive"))
      (node (ref "U4") (pin "22") (pinfunction "P2.1/A9_22") (pintype "bidirectional"))
    )
    (net (code "58") (name "Net-(U4-P2.4{slash}A12)") (class "Default")
      (node (ref "R28") (pin "1") (pinfunction "1_1") (pintype "passive"))
      (node (ref "U4") (pin "25") (pinfunction "P2.4/A12_25") (pintype "bidirectional"))
    )
    (net (code "59") (name "Net-(U4-P2.7{slash}A15)") (class "Default")
      (node (ref "R29") (pin "1") (pinfunction "1_1") (pintype "passive"))
      (node (ref "U4") (pin "28") (pinfunction "P2.7/A15_28") (pintype "bidirectional"))
    )
    (net (code "60") (name "Net-(U4-P3.4{slash}T0)") (class "Default")
      (node (ref "R26") (pin "2") (pinfunction "2_2") (pintype "passive"))
      (node (ref "U4") (pin "14") (pinfunction "P3.4/T0_14") (pintype "bidirectional"))
    )
    (net (code "61") (name "Net-(U4-RST)") (class "Default")
      (node (ref "C10") (pin "2") (pinfunction "2_2") (pintype "passive"))
      (node (ref "R22") (pin "2") (pinfunction "2_2") (pintype "passive"))
      (node (ref "U4") (pin "9") (pinfunction "RST_9") (pintype "input"))
    )
    (net (code "62") (name "Net-(U4-XTAL1)") (class "Default")
      (node (ref "C7") (pin "1") (pinfunction "1_1") (pintype "passive"))
      (node (ref "U4") (pin "19") (pinfunction "XTAL1_19") (pintype "input"))
      (node (ref "Y1") (pin "1") (pinfunction "OSC1_1") (pintype "passive"))
    )
    (net (code "63") (name "Net-(U4-XTAL2)") (class "Default")
      (node (ref "C1") (pin "2") (pinfunction "2_2") (pintype "passive"))
      (node (ref "U4") (pin "18") (pinfunction "XTAL2_18") (pintype "output"))
      (node (ref "Y1") (pin "2") (pinfunction "OSC2_2") (pintype "passive"))
    )
    (net (code "64") (name "unconnected-(C8-Pad1)") (class "Default")
      (node (ref "C8") (pin "1") (pinfunction "1_1") (pintype "passive"))
    )
    (net (code "65") (name "unconnected-(C8-Pad2)") (class "Default")
      (node (ref "C8") (pin "2") (pinfunction "2_2") (pintype "passive"))
    )
    (net (code "66") (name "unconnected-(C8-Pad3)") (class "Default")
      (node (ref "C8") (pin "3") (pinfunction "3_3") (pintype "passive"))
    )
    (net (code "67") (name "unconnected-(C9-Pad1)") (class "Default")
      (node (ref "C9") (pin "1") (pinfunction "1_1") (pintype "passive"))
    )
    (net (code "68") (name "unconnected-(C9-Pad2)") (class "Default")
      (node (ref "C9") (pin "2") (pinfunction "2_2") (pintype "passive"))
    )
    (net (code "69") (name "unconnected-(C9-Pad3)") (class "Default")
      (node (ref "C9") (pin "3") (pinfunction "3_3") (pintype "passive"))
    )
    (net (code "70") (name "unconnected-(DS1-KL-Pad14)") (class "Default")
      (node (ref "DS1") (pin "14") (pinfunction "KL_14") (pintype "passive"))
    )
    (net (code "71") (name "unconnected-(P3-Pad3)") (class "Default")
      (node (ref "P3") (pin "3") (pinfunction "3_3") (pintype "passive"))
    )
    (net (code "72") (name "unconnected-(P3-Pad4)") (class "Default")
      (node (ref "P3") (pin "4") (pinfunction "4_4") (pintype "passive"))
    )
    (net (code "73") (name "unconnected-(R11-Pad1)") (class "Default")
      (node (ref "R11") (pin "1") (pinfunction "1_1") (pintype "passive"))
    )
    (net (code "74") (name "unconnected-(R11-Pad2)") (class "Default")
      (node (ref "R11") (pin "2") (pinfunction "2_2") (pintype "passive"))
    )
    (net (code "75") (name "unconnected-(R12-Pad1)") (class "Default")
      (node (ref "R12") (pin "1") (pinfunction "1_1") (pintype "passive"))
    )
    (net (code "76") (name "unconnected-(R12-Pad2)") (class "Default")
      (node (ref "R12") (pin "2") (pinfunction "2_2") (pintype "passive"))
    )
    (net (code "77") (name "unconnected-(T9-Pad1)") (class "Default")
      (node (ref "T9") (pin "1") (pinfunction "1_1") (pintype "passive"))
    )
    (net (code "78") (name "unconnected-(T14-Pad1)") (class "Default")
      (node (ref "T14") (pin "1") (pinfunction "1_1") (pintype "passive"))
    )
    (net (code "79") (name "unconnected-(T15-Pad1)") (class "Default")
      (node (ref "T15") (pin "1") (pinfunction "1_1") (pintype "passive"))
    )
    (net (code "80") (name "unconnected-(T16-Pad1)") (class "Default")
      (node (ref "T16") (pin "1") (pinfunction "1_1") (pintype "passive"))
    )
    (net (code "81") (name "unconnected-(U4-ALE{slash}~{PROG}-Pad30)") (class "Default")
      (node (ref "U4") (pin "30") (pinfunction "ALE/~{PROG}_30") (pintype "bidirectional"))
    )
    (net (code "82") (name "unconnected-(U4-P1.1{slash}T2EX-Pad2)") (class "Default")
      (node (ref "U4") (pin "2") (pinfunction "P1.1/T2EX_2") (pintype "bidirectional+no_connect"))
    )
    (net (code "83") (name "unconnected-(U4-P1.2{slash}ECI-Pad3)") (class "Default")
      (node (ref "U4") (pin "3") (pinfunction "P1.2/ECI_3") (pintype "bidirectional+no_connect"))
    )
    (net (code "84") (name "unconnected-(U4-P2.2{slash}A10-Pad23)") (class "Default")
      (node (ref "U4") (pin "23") (pinfunction "P2.2/A10_23") (pintype "bidirectional+no_connect"))
    )
    (net (code "85") (name "unconnected-(U4-P2.3{slash}A11-Pad24)") (class "Default")
      (node (ref "U4") (pin "24") (pinfunction "P2.3/A11_24") (pintype "bidirectional+no_connect"))
    )
    (net (code "86") (name "unconnected-(U4-P2.5{slash}A13-Pad26)") (class "Default")
      (node (ref "U4") (pin "26") (pinfunction "P2.5/A13_26") (pintype "bidirectional+no_connect"))
    )
    (net (code "87") (name "unconnected-(U4-P2.6{slash}A14-Pad27)") (class "Default")
      (node (ref "U4") (pin "27") (pinfunction "P2.6/A14_27") (pintype "bidirectional+no_connect"))
    )
    (net (code "88") (name "unconnected-(U4-P3.2{slash}~{INT}0-Pad12)") (class "Default")
      (node (ref "U4") (pin "12") (pinfunction "P3.2/~{INT}0_12") (pintype "bidirectional+no_connect"))
    )
    (net (code "89") (name "unconnected-(U4-P3.3{slash}~{INT}1-Pad13)") (class "Default")
      (node (ref "U4") (pin "13") (pinfunction "P3.3/~{INT}1_13") (pintype "bidirectional+no_connect"))
    )
    (net (code "90") (name "unconnected-(U4-P3.6{slash}~{WR}-Pad16)") (class "Default")
      (node (ref "U4") (pin "16") (pinfunction "P3.6/~{WR}_16") (pintype "bidirectional+no_connect"))
    )
    (net (code "91") (name "unconnected-(U4-P3.7{slash}~{RD}-Pad17)") (class "Default")
      (node (ref "U4") (pin "17") (pinfunction "P3.7/~{RD}_17") (pintype "bidirectional+no_connect"))
    )
    (net (code "92") (name "unconnected-(U4-VCC-Pad40)") (class "Default")
      (node (ref "U4") (pin "40") (pinfunction "VCC_40") (pintype "power_in"))
    )
    (net (code "93") (name "unconnected-(U4-~{PSEN}-Pad29)") (class "Default")
      (node (ref "U4") (pin "29") (pinfunction "~{PSEN}_29") (pintype "output"))
    )
    (net (code "94") (name "unconnected-(Y2-OSC1-Pad1)") (class "Default")
      (node (ref "Y2") (pin "1") (pinfunction "OSC1_1") (pintype "passive"))
    )
    (net (code "95") (name "unconnected-(Y2-OSC2-Pad2)") (class "Default")
      (node (ref "Y2") (pin "2") (pinfunction "OSC2_2") (pintype "passive"))
    )
  )
)
